# FRONT-UNIT-3_5.net
KiCad netlist of a schematic drawn in Altium Designer
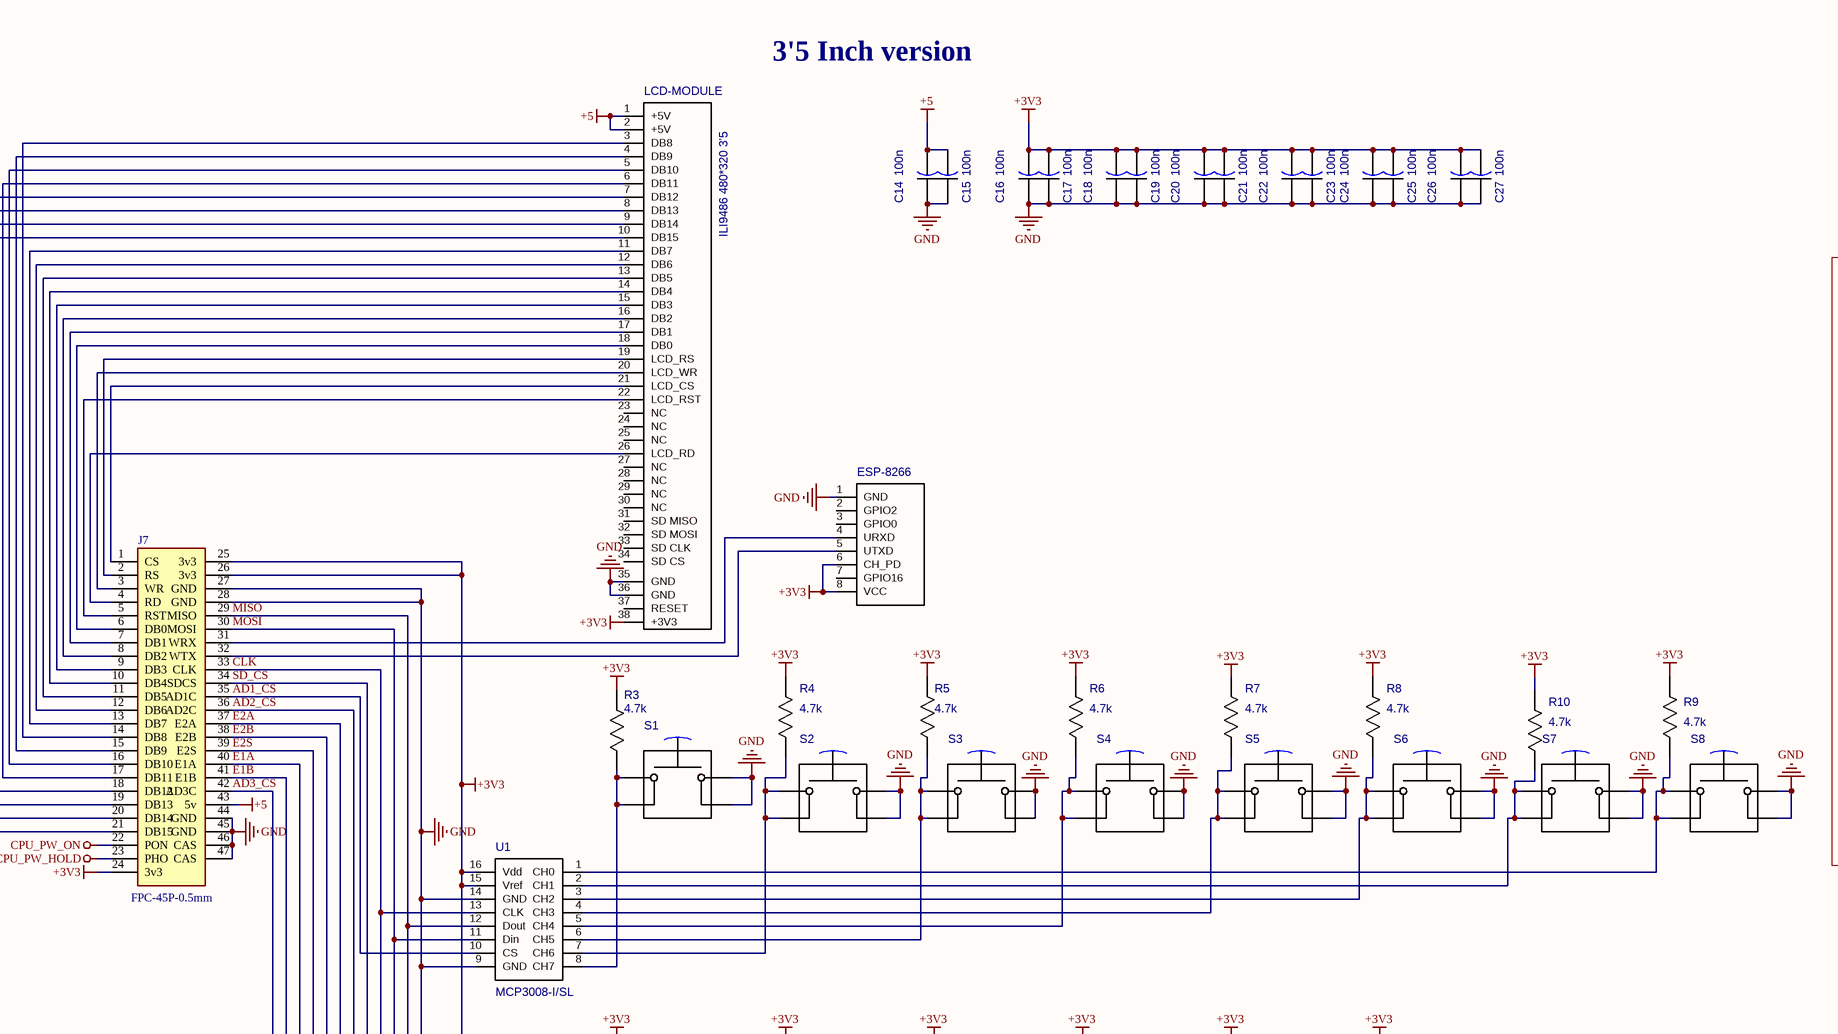
[diagram p0: FRONT-UNIT-3.5.SCHDOC, top left]
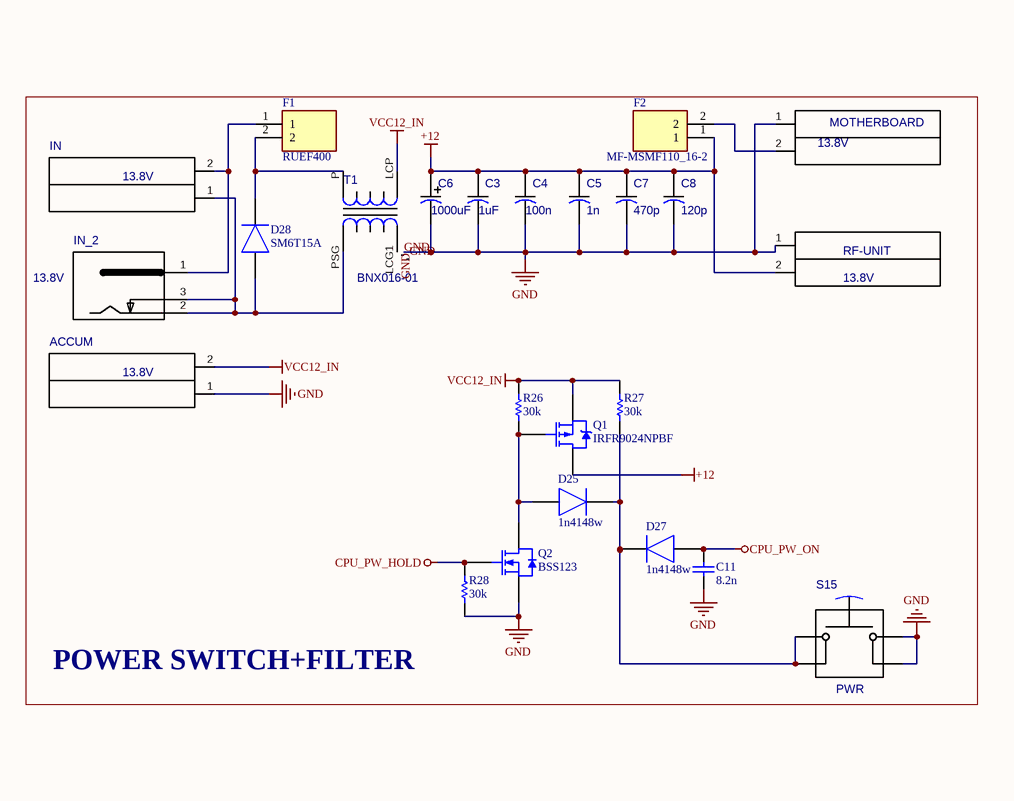
[diagram p1: FRONT-UNIT-3.5.SCHDOC, top right]
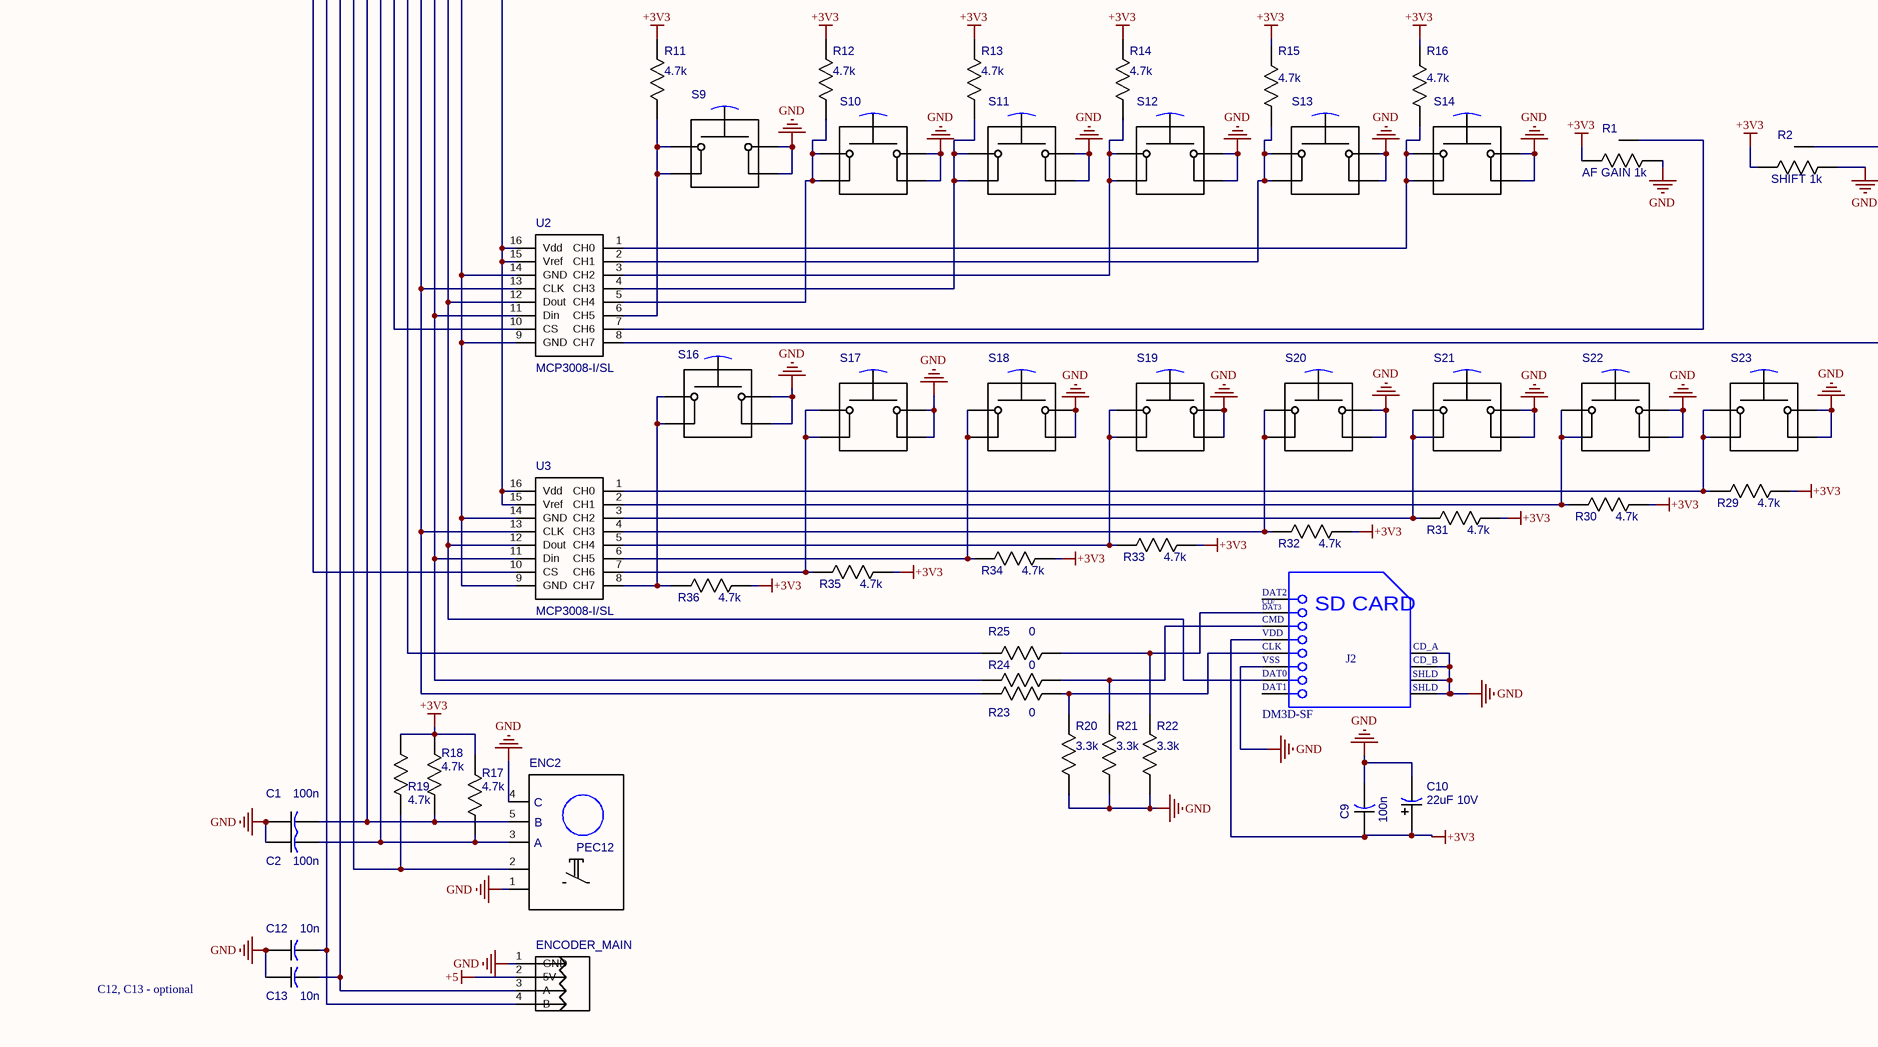
[diagram p2: FRONT-UNIT-3.5.SCHDOC, bottom left]
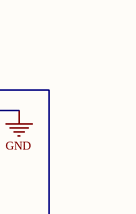
[diagram p3: FRONT-UNIT-3.5.SCHDOC, bottom right]

(export (version "E")
  (design (tool "Eeschema 10.0.6"))
  (components
    (comp (ref "ACCUM")
      (value "13.8V")
      (footprint "JX2")
      (description "JX2")
      (libsource (lib "*") (part "JX2"))
    )
    (comp (ref "C1")
      (value "100n")
      (footprint "CAP_0805")
      (description "CAP_0805")
      (libsource (lib "*") (part "CAP_0805"))
    )
    (comp (ref "C2")
      (value "100n")
      (footprint "CAP_0805")
      (description "CAP_0805")
      (libsource (lib "*") (part "CAP_0805"))
    )
    (comp (ref "C3")
      (value "1uF")
      (footprint "CAP_1206")
      (description "CAP_1206")
      (libsource (lib "*") (part "CAP_1206"))
    )
    (comp (ref "C4")
      (value "100n")
      (footprint "CAP_1206")
      (description "CAP_1206")
      (libsource (lib "*") (part "CAP_1206"))
    )
    (comp (ref "C5")
      (value "1n")
      (footprint "CAP_1206")
      (description "CAP_1206")
      (libsource (lib "*") (part "CAP_1206"))
    )
    (comp (ref "C6")
      (value "1000uF")
      (footprint "CAP250RP")
      (description "CAP250RP")
      (libsource (lib "*") (part "CAP250RP"))
    )
    (comp (ref "C7")
      (value "470p")
      (footprint "CAP_1206")
      (description "CAP_1206")
      (libsource (lib "*") (part "CAP_1206"))
    )
    (comp (ref "C8")
      (value "120p")
      (footprint "CAP_1206")
      (description "CAP_1206")
      (libsource (lib "*") (part "CAP_1206"))
    )
    (comp (ref "C9")
      (value "100n")
      (footprint "CAP_0805")
      (description "CAP_0805")
      (libsource (lib "*") (part "CAP_0805"))
    )
    (comp (ref "C10")
      (value "22uF 10V")
      (footprint "EEEFC_sizeB")
      (description "EEEFC_sizeB")
      (libsource (lib "*") (part "EEEFC_sizeB"))
    )
    (comp (ref "C11")
      (value "8.2n")
      (footprint "CAPC2013X94X50LL20T25")
      (description "CAP_1206")
      (fields
        (field (name "MANUFACTURER") "AVX Interconnect / Elco")
        (field (name "PART NUMBER") "08055C822KAT2A")
      )
      (libsource (lib "Altium Content Vault") (part "CAP"))
    )
    (comp (ref "C12")
      (value "10n")
      (footprint "CAP_0805")
      (description "CAP_0805")
      (libsource (lib "*") (part "CAP_0805"))
    )
    (comp (ref "C13")
      (value "10n")
      (footprint "CAP_0805")
      (description "CAP_0805")
      (libsource (lib "*") (part "CAP_0805"))
    )
    (comp (ref "C14")
      (value "100n")
      (footprint "CAP_0805")
      (description "CAP_0805")
      (libsource (lib "*") (part "CAP_0805"))
    )
    (comp (ref "C15")
      (value "100n")
      (footprint "CAP_0805")
      (description "CAP_0805")
      (libsource (lib "*") (part "CAP_0805"))
    )
    (comp (ref "C16")
      (value "100n")
      (footprint "CAP_0805")
      (description "CAP_0805")
      (libsource (lib "*") (part "CAP_0805"))
    )
    (comp (ref "C17")
      (value "100n")
      (footprint "CAP_0805")
      (description "CAP_0805")
      (libsource (lib "*") (part "CAP_0805"))
    )
    (comp (ref "C18")
      (value "100n")
      (footprint "CAP_0805")
      (description "CAP_0805")
      (libsource (lib "*") (part "CAP_0805"))
    )
    (comp (ref "C19")
      (value "100n")
      (footprint "CAP_0805")
      (description "CAP_0805")
      (libsource (lib "*") (part "CAP_0805"))
    )
    (comp (ref "C20")
      (value "100n")
      (footprint "CAP_0805")
      (description "CAP_0805")
      (libsource (lib "*") (part "CAP_0805"))
    )
    (comp (ref "C21")
      (value "100n")
      (footprint "CAP_0805")
      (description "CAP_0805")
      (libsource (lib "*") (part "CAP_0805"))
    )
    (comp (ref "C22")
      (value "100n")
      (footprint "CAP_0805")
      (description "CAP_0805")
      (libsource (lib "*") (part "CAP_0805"))
    )
    (comp (ref "C23")
      (value "100n")
      (footprint "CAP_0805")
      (description "CAP_0805")
      (libsource (lib "*") (part "CAP_0805"))
    )
    (comp (ref "C24")
      (value "100n")
      (footprint "CAP_0805")
      (description "CAP_0805")
      (libsource (lib "*") (part "CAP_0805"))
    )
    (comp (ref "C25")
      (value "100n")
      (footprint "CAP_0805")
      (description "CAP_0805")
      (libsource (lib "*") (part "CAP_0805"))
    )
    (comp (ref "C26")
      (value "100n")
      (footprint "CAP_0805")
      (description "CAP_0805")
      (libsource (lib "*") (part "CAP_0805"))
    )
    (comp (ref "C27")
      (value "100n")
      (footprint "CAP_0805")
      (description "CAP_0805")
      (libsource (lib "*") (part "CAP_0805"))
    )
    (comp (ref "D25")
      (value "1n4148w")
      (footprint "SamacSys:SOD3716X135N")
      (description "Diode")
      (libsource (lib "*") (part "1n4148w"))
    )
    (comp (ref "D27")
      (value "1n4148w")
      (footprint "SamacSys:SOD3716X135N")
      (description "Diode")
      (libsource (lib "*") (part "1n4148w"))
    )
    (comp (ref "D28")
      (value "SM6T15A")
      (footprint "SamacSys:SMBJ36CATR")
      (description "Diode")
      (fields (field (name "MOUSER PART NUMBER") "511-SM6T15A") (field (name "RS PART NUMBER") "4864915P"))
      (libsource (lib "*") (part "SM6T15A"))
    )
    (comp (ref "ENC2") (value "PEC12") (footprint "PEC12") (libsource (lib "*") (part "PEC12")))
    (comp (ref "ENCODER_MAIN")
      (value "OPTICAL ENCODER")
      (footprint "644456-4")
      (libsource (lib "*") (part "644456-4"))
    )
    (comp (ref "ESP-8266")
      (value "ESP-01 ESP8266")
      (footprint "ESP-01 ESP8266")
      (libsource (lib "*") (part "ESP-01 ESP8266"))
    )
    (comp (ref "F1")
      (value "RUEF400")
      (footprint "SamacSys:RUEF400")
      (description "Fuse")
      (fields (field (name "MOUSER PART NUMBER") "650-RUEF400") (field (name "RS PART NUMBER") "5176837P"))
      (libsource (lib "*") (part "RUEF400"))
    )
    (comp (ref "F2")
      (value "MF-MSMF110_16-2")
      (footprint "SamacSys:FUSC4632X85N")
      (description "Fuse")
      (fields
        (field (name "MANUFACTURER_PART_NUMBER") "MF-MSMF110/16-2")
        (field (name "MOUSER PART NUMBER") "652-MF-MSMF110/16-2")
      )
      (libsource (lib "*") (part "MF-MSMF110_16-2"))
    )
    (comp (ref "IN") (value "13.8V") (footprint "JX2") (description "JX2") (libsource (lib "*") (part "JX2")))
    (comp (ref "IN_2")
      (value "13.8V")
      (footprint "PJ-050B")
      (description "PJ-050B")
      (libsource (lib "*") (part "PJ-050B"))
    )
    (comp (ref "J2")
      (value "DM3D-SF")
      (footprint "HIRO-DM3D-SF_V")
      (fields (field (name "MANUFACTURER") "Hirose Electric"))
      (libsource (lib "Altium Content Vault") (part "CN-SD-8-2SW-2S"))
    )
    (comp (ref "J7")
      (value "FPC-45P-0.5mm")
      (footprint "FRONT-UNIT-3.5:FH12S45S05SH60")
      (description "Connector")
      (fields
        (field (name "MANUFACTURER_PART_NUMBER") "FH12S-45S-0.5SH(55)")
        (field (name "MOUSER PART NUMBER") "798-FH12S-45S-05SH55")
      )
      (libsource (lib "*") (part "FH12S-45S-0.5SH_55_"))
    )
    (comp (ref "LCD-MODULE")
      (value "ILI9486 480*320 3'5")
      (footprint "LCD-MODULE-3.2-480-320")
      (description "LCD-MODULE_3'2_480х320")
      (libsource (lib "FRONT-UNIT") (part "LCD-MODULE_3'2_480х320"))
    )
    (comp (ref "MOTHERBOARD")
      (value "13.8V")
      (footprint "JX2")
      (description "JX2")
      (libsource (lib "*") (part "JX2"))
    )
    (comp (ref "Q1")
      (value "IRFR9024NPBF")
      (footprint "ONSC-DPAK-3-369C-01_V")
      (description "IRFR9024NPBF, Транзистор, Р-канал 55В 11А")
      (fields (field (name "MANUFACTURER") "On Semiconductor") (field (name "PARTNUMBER") "NTD2955G"))
      (libsource (lib "Altium Content Vault") (part "ONSC-PMOS-G1S3D4-3_B"))
    )
    (comp (ref "Q2")
      (value "BSS123")
      (footprint "FAIR-SOT23-3_V")
      (fields (field (name "MANUFACTURER") "Fairchild"))
      (libsource (lib "Altium Content Vault") (part "NEMOS-GSD-3"))
    )
    (comp (ref "R1")
      (value "AF GAIN 1k")
      (footprint "PTV09")
      (description "Adjustable Resistor PTV09")
      (fields (field (name "Comment") "ptv09a-4225f-b102"))
      (libsource (lib "*") (part "PTV09"))
    )
    (comp (ref "R2")
      (value "SHIFT 1k")
      (footprint "PTV09")
      (description "Adjustable Resistor PTV09")
      (fields (field (name "Comment") "ptv09a-4225f-b102"))
      (libsource (lib "*") (part "PTV09"))
    )
    (comp (ref "R3")
      (value "4.7k")
      (footprint "RES_0805")
      (description "RES_0805")
      (libsource (lib "*") (part "RES_0805"))
    )
    (comp (ref "R4")
      (value "4.7k")
      (footprint "RES_0805")
      (description "RES_0805")
      (libsource (lib "*") (part "RES_0805"))
    )
    (comp (ref "R5")
      (value "4.7k")
      (footprint "RES_0805")
      (description "RES_0805")
      (libsource (lib "*") (part "RES_0805"))
    )
    (comp (ref "R6")
      (value "4.7k")
      (footprint "RES_0805")
      (description "RES_0805")
      (libsource (lib "*") (part "RES_0805"))
    )
    (comp (ref "R7")
      (value "4.7k")
      (footprint "RES_0805")
      (description "RES_0805")
      (libsource (lib "*") (part "RES_0805"))
    )
    (comp (ref "R8")
      (value "4.7k")
      (footprint "RES_0805")
      (description "RES_0805")
      (libsource (lib "*") (part "RES_0805"))
    )
    (comp (ref "R9")
      (value "4.7k")
      (footprint "RES_0805")
      (description "RES_0805")
      (libsource (lib "*") (part "RES_0805"))
    )
    (comp (ref "R10")
      (value "4.7k")
      (footprint "RES_0805")
      (description "RES_0805")
      (libsource (lib "*") (part "RES_0805"))
    )
    (comp (ref "R11")
      (value "4.7k")
      (footprint "RES_0805")
      (description "RES_0805")
      (libsource (lib "*") (part "RES_0805"))
    )
    (comp (ref "R12")
      (value "4.7k")
      (footprint "RES_0805")
      (description "RES_0805")
      (libsource (lib "*") (part "RES_0805"))
    )
    (comp (ref "R13")
      (value "4.7k")
      (footprint "RES_0805")
      (description "RES_0805")
      (libsource (lib "*") (part "RES_0805"))
    )
    (comp (ref "R14")
      (value "4.7k")
      (footprint "RES_0805")
      (description "RES_0805")
      (libsource (lib "*") (part "RES_0805"))
    )
    (comp (ref "R15")
      (value "4.7k")
      (footprint "RES_0805")
      (description "RES_0805")
      (libsource (lib "*") (part "RES_0805"))
    )
    (comp (ref "R16")
      (value "4.7k")
      (footprint "RES_0805")
      (description "RES_0805")
      (libsource (lib "*") (part "RES_0805"))
    )
    (comp (ref "R17")
      (value "4.7k")
      (footprint "RES_0805")
      (description "RES_0805")
      (libsource (lib "*") (part "RES_0805"))
    )
    (comp (ref "R18")
      (value "4.7k")
      (footprint "RES_0805")
      (description "RES_0805")
      (libsource (lib "*") (part "RES_0805"))
    )
    (comp (ref "R19")
      (value "4.7k")
      (footprint "RES_0805")
      (description "RES_0805")
      (libsource (lib "*") (part "RES_0805"))
    )
    (comp (ref "R20")
      (value "3.3k")
      (footprint "RES_0805")
      (description "RES_0805")
      (libsource (lib "*") (part "RES_0805"))
    )
    (comp (ref "R21")
      (value "3.3k")
      (footprint "RES_0805")
      (description "RES_0805")
      (libsource (lib "*") (part "RES_0805"))
    )
    (comp (ref "R22")
      (value "3.3k")
      (footprint "RES_0805")
      (description "RES_0805")
      (libsource (lib "*") (part "RES_0805"))
    )
    (comp (ref "R23")
      (value "0")
      (footprint "RES_0805")
      (description "RES_0805")
      (libsource (lib "*") (part "RES_0805"))
    )
    (comp (ref "R24")
      (value "0")
      (footprint "RES_0805")
      (description "RES_0805")
      (libsource (lib "*") (part "RES_0805"))
    )
    (comp (ref "R25")
      (value "0")
      (footprint "RES_0805")
      (description "RES_0805")
      (libsource (lib "*") (part "RES_0805"))
    )
    (comp (ref "R26")
      (value "30k")
      (footprint "RESC2013X60X40NL20T25")
      (description "RES_0805")
      (fields (field (name "MANUFACTURER") "Panasonic") (field (name "PART NUMBER") "ERA-6AEB303V"))
      (libsource (lib "Altium Content Vault") (part "RES"))
    )
    (comp (ref "R27")
      (value "30k")
      (footprint "RESC2013X60X40NL20T25")
      (description "RES_0805")
      (fields (field (name "MANUFACTURER") "Panasonic") (field (name "PART NUMBER") "ERA-6AEB303V"))
      (libsource (lib "Altium Content Vault") (part "RES"))
    )
    (comp (ref "R28")
      (value "30k")
      (footprint "RESC2013X60X40NL20T25")
      (description "RES_0805")
      (fields (field (name "MANUFACTURER") "Panasonic") (field (name "PART NUMBER") "ERA-6AEB303V"))
      (libsource (lib "Altium Content Vault") (part "RES"))
    )
    (comp (ref "R29")
      (value "4.7k")
      (footprint "RES_0805")
      (description "RES_0805")
      (libsource (lib "*") (part "RES_0805"))
    )
    (comp (ref "R30")
      (value "4.7k")
      (footprint "RES_0805")
      (description "RES_0805")
      (libsource (lib "*") (part "RES_0805"))
    )
    (comp (ref "R31")
      (value "4.7k")
      (footprint "RES_0805")
      (description "RES_0805")
      (libsource (lib "*") (part "RES_0805"))
    )
    (comp (ref "R32")
      (value "4.7k")
      (footprint "RES_0805")
      (description "RES_0805")
      (libsource (lib "*") (part "RES_0805"))
    )
    (comp (ref "R33")
      (value "4.7k")
      (footprint "RES_0805")
      (description "RES_0805")
      (libsource (lib "*") (part "RES_0805"))
    )
    (comp (ref "R34")
      (value "4.7k")
      (footprint "RES_0805")
      (description "RES_0805")
      (libsource (lib "*") (part "RES_0805"))
    )
    (comp (ref "R35")
      (value "4.7k")
      (footprint "RES_0805")
      (description "RES_0805")
      (libsource (lib "*") (part "RES_0805"))
    )
    (comp (ref "R36")
      (value "4.7k")
      (footprint "RES_0805")
      (description "RES_0805")
      (libsource (lib "*") (part "RES_0805"))
    )
    (comp (ref "RF-UNIT")
      (value "13.8V")
      (footprint "JX2")
      (description "JX2")
      (libsource (lib "*") (part "JX2"))
    )
    (comp (ref "S1")
      (value "PTS645SK50LFS")
      (footprint "PTS645SK50LFS")
      (fields (field (name "LCSC PART #") "test"))
      (libsource (lib "*") (part "PTS645SK50LFS"))
    )
    (comp (ref "S2")
      (value "PTS645SK50LFS")
      (footprint "PTS645SK50LFS")
      (libsource (lib "*") (part "PTS645SK50LFS"))
    )
    (comp (ref "S3")
      (value "PTS645SK50LFS")
      (footprint "PTS645SK50LFS")
      (libsource (lib "*") (part "PTS645SK50LFS"))
    )
    (comp (ref "S4")
      (value "PTS645SK50LFS")
      (footprint "PTS645SK50LFS")
      (libsource (lib "*") (part "PTS645SK50LFS"))
    )
    (comp (ref "S5")
      (value "PTS645SK50LFS")
      (footprint "PTS645SK50LFS")
      (libsource (lib "*") (part "PTS645SK50LFS"))
    )
    (comp (ref "S6")
      (value "PTS645SK50LFS")
      (footprint "PTS645SK50LFS")
      (libsource (lib "*") (part "PTS645SK50LFS"))
    )
    (comp (ref "S7")
      (value "PTS645SK50LFS")
      (footprint "PTS645SK50LFS")
      (libsource (lib "*") (part "PTS645SK50LFS"))
    )
    (comp (ref "S8")
      (value "PTS645SK50LFS")
      (footprint "PTS645SK50LFS")
      (libsource (lib "*") (part "PTS645SK50LFS"))
    )
    (comp (ref "S9")
      (value "PTS645SK50LFS")
      (footprint "PTS645SK50LFS")
      (libsource (lib "*") (part "PTS645SK50LFS"))
    )
    (comp (ref "S10")
      (value "PTS645SK50LFS")
      (footprint "PTS645SK50LFS")
      (libsource (lib "*") (part "PTS645SK50LFS"))
    )
    (comp (ref "S11")
      (value "PTS645SK50LFS")
      (footprint "PTS645SK50LFS")
      (libsource (lib "*") (part "PTS645SK50LFS"))
    )
    (comp (ref "S12")
      (value "PTS645SK50LFS")
      (footprint "PTS645SK50LFS")
      (libsource (lib "*") (part "PTS645SK50LFS"))
    )
    (comp (ref "S13")
      (value "PTS645SK50LFS")
      (footprint "PTS645SK50LFS")
      (libsource (lib "*") (part "PTS645SK50LFS"))
    )
    (comp (ref "S14")
      (value "PTS645SK50LFS")
      (footprint "PTS645SK50LFS")
      (libsource (lib "*") (part "PTS645SK50LFS"))
    )
    (comp (ref "S15")
      (value "PWR")
      (footprint "PTS645SK50LFS")
      (description "PTS645SK50LFS")
      (libsource (lib "*") (part "PTS645SK50LFS"))
    )
    (comp (ref "S16")
      (value "PTS645SK50LFS")
      (footprint "PTS645SK50LFS")
      (libsource (lib "*") (part "PTS645SK50LFS"))
    )
    (comp (ref "S17")
      (value "PTS645SK50LFS")
      (footprint "PTS645SK50LFS")
      (libsource (lib "*") (part "PTS645SK50LFS"))
    )
    (comp (ref "S18")
      (value "PTS645SK50LFS")
      (footprint "PTS645SK50LFS")
      (libsource (lib "*") (part "PTS645SK50LFS"))
    )
    (comp (ref "S19")
      (value "PTS645SK50LFS")
      (footprint "PTS645SK50LFS")
      (libsource (lib "*") (part "PTS645SK50LFS"))
    )
    (comp (ref "S20")
      (value "PTS645SK50LFS")
      (footprint "PTS645SK50LFS")
      (libsource (lib "*") (part "PTS645SK50LFS"))
    )
    (comp (ref "S21")
      (value "PTS645SK50LFS")
      (footprint "PTS645SK50LFS")
      (libsource (lib "*") (part "PTS645SK50LFS"))
    )
    (comp (ref "S22")
      (value "PTS645SK50LFS")
      (footprint "PTS645SK50LFS")
      (libsource (lib "*") (part "PTS645SK50LFS"))
    )
    (comp (ref "S23")
      (value "PTS645SK50LFS")
      (footprint "PTS645SK50LFS")
      (libsource (lib "*") (part "PTS645SK50LFS"))
    )
    (comp (ref "T1")
      (value "BNX016-01")
      (footprint "TRANSF_ICORE")
      (libsource (lib "*") (part "TRANSF_ICORE"))
    )
    (comp (ref "U1")
      (value "MCP3008-I/SL")
      (footprint "MCP3008-I/SL")
      (libsource (lib "*") (part "MCP3008-I/SL"))
    )
    (comp (ref "U2")
      (value "MCP3008-I/SL")
      (footprint "MCP3008-I/SL")
      (libsource (lib "*") (part "MCP3008-I/SL"))
    )
    (comp (ref "U3")
      (value "MCP3008-I/SL")
      (footprint "MCP3008-I/SL")
      (libsource (lib "*") (part "MCP3008-I/SL"))
    )
  )
  (nets
    (net (code "1") (name "+3V3") (class "Default")
      (node (ref "C10") (pin "1") (pinfunction "PLUS_1") (pintype "passive"))
      (node (ref "C16") (pin "2") (pinfunction "2_2") (pintype "passive"))
      (node (ref "C17") (pin "2") (pinfunction "2_2") (pintype "passive"))
      (node (ref "C18") (pin "2") (pinfunction "2_2") (pintype "passive"))
      (node (ref "C19") (pin "2") (pinfunction "2_2") (pintype "passive"))
      (node (ref "C20") (pin "2") (pinfunction "2_2") (pintype "passive"))
      (node (ref "C21") (pin "2") (pinfunction "2_2") (pintype "passive"))
      (node (ref "C22") (pin "2") (pinfunction "2_2") (pintype "passive"))
      (node (ref "C23") (pin "2") (pinfunction "2_2") (pintype "passive"))
      (node (ref "C24") (pin "2") (pinfunction "2_2") (pintype "passive"))
      (node (ref "C25") (pin "2") (pinfunction "2_2") (pintype "passive"))
      (node (ref "C26") (pin "2") (pinfunction "2_2") (pintype "passive"))
      (node (ref "C27") (pin "2") (pinfunction "2_2") (pintype "passive"))
      (node (ref "C9") (pin "1") (pinfunction "1_1") (pintype "passive"))
      (node (ref "ESP-8266") (pin "6") (pinfunction "CH_PD_6") (pintype "passive"))
      (node (ref "ESP-8266") (pin "8") (pinfunction "VCC_8") (pintype "passive"))
      (node (ref "J2") (pin "4") (pinfunction "VDD_4") (pintype "passive"))
      (node (ref "J7") (pin "24") (pinfunction "3v3_24") (pintype "passive"))
      (node (ref "J7") (pin "25") (pinfunction "3v3_25") (pintype "passive"))
      (node (ref "J7") (pin "26") (pinfunction "3v3_26") (pintype "passive"))
      (node (ref "LCD-MODULE") (pin "38") (pinfunction "+3V3_38") (pintype "passive"))
      (node (ref "R1") (pin "1") (pinfunction "CW_1") (pintype "passive"))
      (node (ref "R10") (pin "2") (pinfunction "2_2") (pintype "passive"))
      (node (ref "R11") (pin "2") (pinfunction "2_2") (pintype "passive"))
      (node (ref "R12") (pin "2") (pinfunction "2_2") (pintype "passive"))
      (node (ref "R13") (pin "2") (pinfunction "2_2") (pintype "passive"))
      (node (ref "R14") (pin "2") (pinfunction "2_2") (pintype "passive"))
      (node (ref "R15") (pin "2") (pinfunction "2_2") (pintype "passive"))
      (node (ref "R16") (pin "2") (pinfunction "2_2") (pintype "passive"))
      (node (ref "R17") (pin "2") (pinfunction "2_2") (pintype "passive"))
      (node (ref "R18") (pin "2") (pinfunction "2_2") (pintype "passive"))
      (node (ref "R19") (pin "2") (pinfunction "2_2") (pintype "passive"))
      (node (ref "R2") (pin "1") (pinfunction "CW_1") (pintype "passive"))
      (node (ref "R29") (pin "2") (pinfunction "2_2") (pintype "passive"))
      (node (ref "R3") (pin "2") (pinfunction "2_2") (pintype "passive"))
      (node (ref "R30") (pin "2") (pinfunction "2_2") (pintype "passive"))
      (node (ref "R31") (pin "2") (pinfunction "2_2") (pintype "passive"))
      (node (ref "R32") (pin "2") (pinfunction "2_2") (pintype "passive"))
      (node (ref "R33") (pin "2") (pinfunction "2_2") (pintype "passive"))
      (node (ref "R34") (pin "2") (pinfunction "2_2") (pintype "passive"))
      (node (ref "R35") (pin "2") (pinfunction "2_2") (pintype "passive"))
      (node (ref "R36") (pin "2") (pinfunction "2_2") (pintype "passive"))
      (node (ref "R4") (pin "2") (pinfunction "2_2") (pintype "passive"))
      (node (ref "R5") (pin "2") (pinfunction "2_2") (pintype "passive"))
      (node (ref "R6") (pin "2") (pinfunction "2_2") (pintype "passive"))
      (node (ref "R7") (pin "2") (pinfunction "2_2") (pintype "passive"))
      (node (ref "R8") (pin "2") (pinfunction "2_2") (pintype "passive"))
      (node (ref "R9") (pin "2") (pinfunction "2_2") (pintype "passive"))
      (node (ref "U1") (pin "15") (pinfunction "Vref_15") (pintype "passive"))
      (node (ref "U1") (pin "16") (pinfunction "Vdd_16") (pintype "passive"))
      (node (ref "U2") (pin "15") (pinfunction "Vref_15") (pintype "passive"))
      (node (ref "U2") (pin "16") (pinfunction "Vdd_16") (pintype "passive"))
      (node (ref "U3") (pin "15") (pinfunction "Vref_15") (pintype "passive"))
      (node (ref "U3") (pin "16") (pinfunction "Vdd_16") (pintype "passive"))
    )
    (net (code "2") (name "+5") (class "Default")
      (node (ref "C14") (pin "2") (pinfunction "2_2") (pintype "passive"))
      (node (ref "C15") (pin "2") (pinfunction "2_2") (pintype "passive"))
      (node (ref "ENCODER_MAIN") (pin "2") (pinfunction "5V_2") (pintype "passive"))
      (node (ref "J7") (pin "43") (pinfunction "5v_43") (pintype "passive"))
      (node (ref "LCD-MODULE") (pin "1") (pinfunction "+5V_1") (pintype "passive"))
      (node (ref "LCD-MODULE") (pin "2") (pinfunction "+5V_2") (pintype "passive"))
    )
    (net (code "3") (name "+12") (class "Default")
      (node (ref "C3") (pin "1") (pinfunction "1_1") (pintype "passive"))
      (node (ref "C4") (pin "1") (pinfunction "1_1") (pintype "passive"))
      (node (ref "C5") (pin "1") (pinfunction "1_1") (pintype "passive"))
      (node (ref "C6") (pin "1") (pinfunction "PLUS_1") (pintype "passive"))
      (node (ref "C7") (pin "1") (pinfunction "1_1") (pintype "passive"))
      (node (ref "C8") (pin "1") (pinfunction "1_1") (pintype "passive"))
      (node (ref "F2") (pin "1") (pinfunction "1_1") (pintype "passive"))
      (node (ref "Q1") (pin "4") (pinfunction "D_4") (pintype "passive"))
      (node (ref "RF-UNIT") (pin "2") (pinfunction "1_2") (pintype "passive"))
    )
    (net (code "4") (name "/AD1_CS") (class "Default")
      (node (ref "J7") (pin "35") (pinfunction "AD1C_35") (pintype "passive"))
      (node (ref "U1") (pin "10") (pinfunction "CS_10") (pintype "passive"))
    )
    (net (code "5") (name "/AD2_CS") (class "Default")
      (node (ref "J7") (pin "36") (pinfunction "AD2C_36") (pintype "passive"))
      (node (ref "U2") (pin "10") (pinfunction "CS_10") (pintype "passive"))
    )
    (net (code "6") (name "/AD3_CS") (class "Default")
      (node (ref "J7") (pin "42") (pinfunction "AD3C_42") (pintype "passive"))
      (node (ref "U3") (pin "10") (pinfunction "CS_10") (pintype "passive"))
    )
    (net (code "7") (name "/CLK") (class "Default")
      (node (ref "J7") (pin "33") (pinfunction "CLK_33") (pintype "passive"))
      (node (ref "R23") (pin "2") (pinfunction "2_2") (pintype "passive"))
      (node (ref "U1") (pin "13") (pinfunction "CLK_13") (pintype "passive"))
      (node (ref "U2") (pin "13") (pinfunction "CLK_13") (pintype "passive"))
      (node (ref "U3") (pin "13") (pinfunction "CLK_13") (pintype "passive"))
    )
    (net (code "8") (name "/E1A") (class "Default")
      (node (ref "C13") (pin "2") (pinfunction "2_2") (pintype "passive"))
      (node (ref "ENCODER_MAIN") (pin "3") (pinfunction "A_3") (pintype "passive"))
      (node (ref "J7") (pin "40") (pinfunction "E1A_40") (pintype "passive"))
    )
    (net (code "9") (name "/E1B") (class "Default")
      (node (ref "C12") (pin "2") (pinfunction "2_2") (pintype "passive"))
      (node (ref "ENCODER_MAIN") (pin "4") (pinfunction "B_4") (pintype "passive"))
      (node (ref "J7") (pin "41") (pinfunction "E1B_41") (pintype "passive"))
    )
    (net (code "10") (name "/E2A") (class "Default")
      (node (ref "C2") (pin "2") (pinfunction "2_2") (pintype "passive"))
      (node (ref "ENC2") (pin "3") (pinfunction "A_3") (pintype "passive"))
      (node (ref "J7") (pin "37") (pinfunction "E2A_37") (pintype "passive"))
      (node (ref "R17") (pin "1") (pinfunction "1_1") (pintype "passive"))
    )
    (net (code "11") (name "/E2B") (class "Default")
      (node (ref "C1") (pin "2") (pinfunction "2_2") (pintype "passive"))
      (node (ref "ENC2") (pin "5") (pinfunction "B_5") (pintype "passive"))
      (node (ref "J7") (pin "38") (pinfunction "E2B_38") (pintype "passive"))
      (node (ref "R18") (pin "1") (pinfunction "1_1") (pintype "passive"))
    )
    (net (code "12") (name "/E2S") (class "Default")
      (node (ref "ENC2") (pin "2") (pinfunction "2_2") (pintype "passive"))
      (node (ref "J7") (pin "39") (pinfunction "E2S_39") (pintype "passive"))
      (node (ref "R19") (pin "1") (pinfunction "1_1") (pintype "passive"))
    )
    (net (code "13") (name "/MISO") (class "Default")
      (node (ref "J2") (pin "7") (pinfunction "DAT0_7") (pintype "passive"))
      (node (ref "J7") (pin "29") (pinfunction "MISO_29") (pintype "passive"))
      (node (ref "U1") (pin "12") (pinfunction "Dout_12") (pintype "passive"))
      (node (ref "U2") (pin "12") (pinfunction "Dout_12") (pintype "passive"))
      (node (ref "U3") (pin "12") (pinfunction "Dout_12") (pintype "passive"))
    )
    (net (code "14") (name "/MOSI") (class "Default")
      (node (ref "J7") (pin "30") (pinfunction "MOSI_30") (pintype "passive"))
      (node (ref "R24") (pin "2") (pinfunction "2_2") (pintype "passive"))
      (node (ref "U1") (pin "11") (pinfunction "Din_11") (pintype "passive"))
      (node (ref "U2") (pin "11") (pinfunction "Din_11") (pintype "passive"))
      (node (ref "U3") (pin "11") (pinfunction "Din_11") (pintype "passive"))
    )
    (net (code "15") (name "/SD_CS") (class "Default")
      (node (ref "J7") (pin "34") (pinfunction "SDCS_34") (pintype "passive"))
      (node (ref "R25") (pin "2") (pinfunction "2_2") (pintype "passive"))
    )
    (net (code "16") (name "CPU_PW_HOLD") (class "Default")
      (node (ref "J7") (pin "23") (pinfunction "PHO_23") (pintype "passive"))
      (node (ref "Q2") (pin "1") (pinfunction "G_1") (pintype "passive"))
      (node (ref "R28") (pin "2") (pinfunction "2_2") (pintype "passive"))
    )
    (net (code "17") (name "CPU_PW_ON") (class "Default")
      (node (ref "C11") (pin "2") (pinfunction "2_2") (pintype "passive"))
      (node (ref "D27") (pin "2") (pinfunction "A_2") (pintype "passive"))
      (node (ref "J7") (pin "22") (pinfunction "PON_22") (pintype "passive"))
    )
    (net (code "18") (name "GND") (class "Default")
      (node (ref "ACCUM") (pin "1") (pinfunction "2_1") (pintype "passive"))
      (node (ref "C1") (pin "1") (pinfunction "1_1") (pintype "passive"))
      (node (ref "C10") (pin "2") (pinfunction "MINUS_2") (pintype "passive"))
      (node (ref "C11") (pin "1") (pinfunction "1_1") (pintype "passive"))
      (node (ref "C12") (pin "1") (pinfunction "1_1") (pintype "passive"))
      (node (ref "C13") (pin "1") (pinfunction "1_1") (pintype "passive"))
      (node (ref "C14") (pin "1") (pinfunction "1_1") (pintype "passive"))
      (node (ref "C15") (pin "1") (pinfunction "1_1") (pintype "passive"))
      (node (ref "C16") (pin "1") (pinfunction "1_1") (pintype "passive"))
      (node (ref "C17") (pin "1") (pinfunction "1_1") (pintype "passive"))
      (node (ref "C18") (pin "1") (pinfunction "1_1") (pintype "passive"))
      (node (ref "C19") (pin "1") (pinfunction "1_1") (pintype "passive"))
      (node (ref "C2") (pin "1") (pinfunction "1_1") (pintype "passive"))
      (node (ref "C20") (pin "1") (pinfunction "1_1") (pintype "passive"))
      (node (ref "C21") (pin "1") (pinfunction "1_1") (pintype "passive"))
      (node (ref "C22") (pin "1") (pinfunction "1_1") (pintype "passive"))
      (node (ref "C23") (pin "1") (pinfunction "1_1") (pintype "passive"))
      (node (ref "C24") (pin "1") (pinfunction "1_1") (pintype "passive"))
      (node (ref "C25") (pin "1") (pinfunction "1_1") (pintype "passive"))
      (node (ref "C26") (pin "1") (pinfunction "1_1") (pintype "passive"))
      (node (ref "C27") (pin "1") (pinfunction "1_1") (pintype "passive"))
      (node (ref "C3") (pin "2") (pinfunction "2_2") (pintype "passive"))
      (node (ref "C4") (pin "2") (pinfunction "2_2") (pintype "passive"))
      (node (ref "C5") (pin "2") (pinfunction "2_2") (pintype "passive"))
      (node (ref "C6") (pin "2") (pinfunction "MINUS_2") (pintype "passive"))
      (node (ref "C7") (pin "2") (pinfunction "2_2") (pintype "passive"))
      (node (ref "C8") (pin "2") (pinfunction "2_2") (pintype "passive"))
      (node (ref "C9") (pin "2") (pinfunction "2_2") (pintype "passive"))
      (node (ref "ENC2") (pin "1") (pinfunction "1_1") (pintype "passive"))
      (node (ref "ENC2") (pin "4") (pinfunction "C_4") (pintype "passive"))
      (node (ref "ENCODER_MAIN") (pin "1") (pinfunction "GND_1") (pintype "passive"))
      (node (ref "ESP-8266") (pin "1") (pinfunction "GND_1") (pintype "passive"))
      (node (ref "J2") (pin "10") (pinfunction "CD_B_10") (pintype "passive"))
      (node (ref "J2") (pin "11") (pinfunction "SHLD1_11") (pintype "passive"))
      (node (ref "J2") (pin "12") (pinfunction "SHLD2_12") (pintype "passive"))
      (node (ref "J2") (pin "13") (pinfunction "SHLD3_13") (pintype "passive"))
      (node (ref "J2") (pin "14") (pinfunction "SHLD4_14") (pintype "passive"))
      (node (ref "J2") (pin "6") (pinfunction "VSS2_6") (pintype "passive"))
      (node (ref "J2") (pin "9") (pinfunction "CD_A_9") (pintype "passive"))
      (node (ref "J7") (pin "27") (pinfunction "GND_27") (pintype "passive"))
      (node (ref "J7") (pin "28") (pinfunction "GND_28") (pintype "passive"))
      (node (ref "J7") (pin "44") (pinfunction "GND_44") (pintype "passive"))
      (node (ref "J7") (pin "45") (pinfunction "GND_45") (pintype "passive"))
      (node (ref "J7") (pin "46") (pinfunction "CAS_46") (pintype "passive"))
      (node (ref "J7") (pin "47") (pinfunction "CAS_47") (pintype "passive"))
      (node (ref "LCD-MODULE") (pin "35") (pinfunction "GND_35") (pintype "passive"))
      (node (ref "LCD-MODULE") (pin "36") (pinfunction "GND_36") (pintype "passive"))
      (node (ref "MOTHERBOARD") (pin "1") (pinfunction "2_1") (pintype "passive"))
      (node (ref "Q2") (pin "2") (pinfunction "S_2") (pintype "passive"))
      (node (ref "R1") (pin "3") (pinfunction "CCW_3") (pintype "passive"))
      (node (ref "R2") (pin "3") (pinfunction "CCW_3") (pintype "passive"))
      (node (ref "R20") (pin "1") (pinfunction "1_1") (pintype "passive"))
      (node (ref "R21") (pin "1") (pinfunction "1_1") (pintype "passive"))
      (node (ref "R22") (pin "1") (pinfunction "1_1") (pintype "passive"))
      (node (ref "R28") (pin "1") (pinfunction "1_1") (pintype "passive"))
      (node (ref "RF-UNIT") (pin "1") (pinfunction "2_1") (pintype "passive"))
      (node (ref "S1") (pin "3") (pinfunction "B_3") (pintype "passive"))
      (node (ref "S1") (pin "4") (pinfunction "B_4") (pintype "passive"))
      (node (ref "S10") (pin "3") (pinfunction "B_3") (pintype "passive"))
      (node (ref "S10") (pin "4") (pinfunction "B_4") (pintype "passive"))
      (node (ref "S11") (pin "3") (pinfunction "B_3") (pintype "passive"))
      (node (ref "S11") (pin "4") (pinfunction "B_4") (pintype "passive"))
      (node (ref "S12") (pin "3") (pinfunction "B_3") (pintype "passive"))
      (node (ref "S12") (pin "4") (pinfunction "B_4") (pintype "passive"))
      (node (ref "S13") (pin "3") (pinfunction "B_3") (pintype "passive"))
      (node (ref "S13") (pin "4") (pinfunction "B_4") (pintype "passive"))
      (node (ref "S14") (pin "3") (pinfunction "B_3") (pintype "passive"))
      (node (ref "S14") (pin "4") (pinfunction "B_4") (pintype "passive"))
      (node (ref "S15") (pin "3") (pinfunction "B_3") (pintype "passive"))
      (node (ref "S15") (pin "4") (pinfunction "B_4") (pintype "passive"))
      (node (ref "S16") (pin "3") (pinfunction "B_3") (pintype "passive"))
      (node (ref "S16") (pin "4") (pinfunction "B_4") (pintype "passive"))
      (node (ref "S17") (pin "3") (pinfunction "B_3") (pintype "passive"))
      (node (ref "S17") (pin "4") (pinfunction "B_4") (pintype "passive"))
      (node (ref "S18") (pin "3") (pinfunction "B_3") (pintype "passive"))
      (node (ref "S18") (pin "4") (pinfunction "B_4") (pintype "passive"))
      (node (ref "S19") (pin "3") (pinfunction "B_3") (pintype "passive"))
      (node (ref "S19") (pin "4") (pinfunction "B_4") (pintype "passive"))
      (node (ref "S2") (pin "3") (pinfunction "B_3") (pintype "passive"))
      (node (ref "S2") (pin "4") (pinfunction "B_4") (pintype "passive"))
      (node (ref "S20") (pin "3") (pinfunction "B_3") (pintype "passive"))
      (node (ref "S20") (pin "4") (pinfunction "B_4") (pintype "passive"))
      (node (ref "S21") (pin "3") (pinfunction "B_3") (pintype "passive"))
      (node (ref "S21") (pin "4") (pinfunction "B_4") (pintype "passive"))
      (node (ref "S22") (pin "3") (pinfunction "B_3") (pintype "passive"))
      (node (ref "S22") (pin "4") (pinfunction "B_4") (pintype "passive"))
      (node (ref "S23") (pin "3") (pinfunction "B_3") (pintype "passive"))
      (node (ref "S23") (pin "4") (pinfunction "B_4") (pintype "passive"))
      (node (ref "S3") (pin "3") (pinfunction "B_3") (pintype "passive"))
      (node (ref "S3") (pin "4") (pinfunction "B_4") (pintype "passive"))
      (node (ref "S4") (pin "3") (pinfunction "B_3") (pintype "passive"))
      (node (ref "S4") (pin "4") (pinfunction "B_4") (pintype "passive"))
      (node (ref "S5") (pin "3") (pinfunction "B_3") (pintype "passive"))
      (node (ref "S5") (pin "4") (pinfunction "B_4") (pintype "passive"))
      (node (ref "S6") (pin "3") (pinfunction "B_3") (pintype "passive"))
      (node (ref "S6") (pin "4") (pinfunction "B_4") (pintype "passive"))
      (node (ref "S7") (pin "3") (pinfunction "B_3") (pintype "passive"))
      (node (ref "S7") (pin "4") (pinfunction "B_4") (pintype "passive"))
      (node (ref "S8") (pin "3") (pinfunction "B_3") (pintype "passive"))
      (node (ref "S8") (pin "4") (pinfunction "B_4") (pintype "passive"))
      (node (ref "S9") (pin "3") (pinfunction "B_3") (pintype "passive"))
      (node (ref "S9") (pin "4") (pinfunction "B_4") (pintype "passive"))
      (node (ref "T1") (pin "LCG1") (pinfunction "S2_LCG1") (pintype "passive"))
      (node (ref "T1") (pin "LCG2") (pinfunction "0_LCG2") (pintype "passive"))
      (node (ref "T1") (pin "LCG3") (pinfunction "0_LCG3") (pintype "passive"))
      (node (ref "U1") (pin "14") (pinfunction "GND_14") (pintype "passive"))
      (node (ref "U1") (pin "9") (pinfunction "GND_9") (pintype "passive"))
      (node (ref "U2") (pin "14") (pinfunction "GND_14") (pintype "passive"))
      (node (ref "U2") (pin "9") (pinfunction "GND_9") (pintype "passive"))
      (node (ref "U3") (pin "14") (pinfunction "GND_14") (pintype "passive"))
      (node (ref "U3") (pin "9") (pinfunction "GND_9") (pintype "passive"))
    )
    (net (code "19") (name "Net-(D25-A)") (class "Default")
      (node (ref "D25") (pin "2") (pinfunction "A_2") (pintype "passive"))
      (node (ref "Q1") (pin "1") (pinfunction "G_1") (pintype "passive"))
      (node (ref "Q2") (pin "3") (pinfunction "D_3") (pintype "passive"))
      (node (ref "R26") (pin "1") (pinfunction "1_1") (pintype "passive"))
    )
    (net (code "20") (name "Net-(D25-K)") (class "Default")
      (node (ref "D25") (pin "1") (pinfunction "K_1") (pintype "passive"))
      (node (ref "D27") (pin "1") (pinfunction "K_1") (pintype "passive"))
      (node (ref "R27") (pin "1") (pinfunction "1_1") (pintype "passive"))
      (node (ref "S15") (pin "1") (pinfunction "A_1") (pintype "passive"))
      (node (ref "S15") (pin "2") (pinfunction "A_2") (pintype "passive"))
    )
    (net (code "21") (name "Net-(D28-A)") (class "Default")
      (node (ref "D28") (pin "2") (pinfunction "A_2") (pintype "passive"))
      (node (ref "IN") (pin "1") (pinfunction "2_1") (pintype "passive"))
      (node (ref "IN_2") (pin "2") (pinfunction "2_2") (pintype "passive"))
      (node (ref "IN_2") (pin "3") (pinfunction "3_3") (pintype "passive"))
      (node (ref "T1") (pin "PSG") (pinfunction "S1_PSG") (pintype "passive"))
    )
    (net (code "22") (name "Net-(D28-K)") (class "Default")
      (node (ref "D28") (pin "1") (pinfunction "K_1") (pintype "passive"))
      (node (ref "F1") (pin "2") (pinfunction "2_2") (pintype "passive"))
      (node (ref "T1") (pin "P") (pinfunction "P1_P") (pintype "passive"))
    )
    (net (code "23") (name "Net-(ESP-8266-URXD)") (class "Default")
      (node (ref "ESP-8266") (pin "4") (pinfunction "URXD_4") (pintype "passive"))
      (node (ref "J7") (pin "31") (pinfunction "WRX_31") (pintype "passive"))
    )
    (net (code "24") (name "Net-(ESP-8266-UTXD)") (class "Default")
      (node (ref "ESP-8266") (pin "5") (pinfunction "UTXD_5") (pintype "passive"))
      (node (ref "J7") (pin "32") (pinfunction "WTX_32") (pintype "passive"))
    )
    (net (code "25") (name "Net-(IN-1)") (class "Default")
      (node (ref "F1") (pin "1") (pinfunction "1_1") (pintype "passive"))
      (node (ref "IN") (pin "2") (pinfunction "1_2") (pintype "passive"))
      (node (ref "IN_2") (pin "1") (pinfunction "1_1") (pintype "passive"))
    )
    (net (code "26") (name "Net-(J2-CLK)") (class "Default")
      (node (ref "J2") (pin "5") (pinfunction "CLK_5") (pintype "passive"))
      (node (ref "R20") (pin "2") (pinfunction "2_2") (pintype "passive"))
      (node (ref "R23") (pin "1") (pinfunction "1_1") (pintype "passive"))
    )
    (net (code "27") (name "Net-(J2-CMD)") (class "Default")
      (node (ref "J2") (pin "2") (pinfunction "CMD_2") (pintype "passive"))
      (node (ref "R22") (pin "2") (pinfunction "2_2") (pintype "passive"))
      (node (ref "R25") (pin "1") (pinfunction "1_1") (pintype "passive"))
    )
    (net (code "28") (name "Net-(J2-VSS1)") (class "Default")
      (node (ref "J2") (pin "3") (pinfunction "VSS1_3") (pintype "passive"))
      (node (ref "R21") (pin "2") (pinfunction "2_2") (pintype "passive"))
      (node (ref "R24") (pin "1") (pinfunction "1_1") (pintype "passive"))
    )
    (net (code "29") (name "Net-(J7-CS)") (class "Default")
      (node (ref "J7") (pin "1") (pinfunction "CS_1") (pintype "passive"))
      (node (ref "LCD-MODULE") (pin "21") (pinfunction "LCD_CS_21") (pintype "passive"))
    )
    (net (code "30") (name "Net-(J7-DB0)") (class "Default")
      (node (ref "J7") (pin "6") (pinfunction "DB0_6") (pintype "passive"))
      (node (ref "LCD-MODULE") (pin "18") (pinfunction "DB0_18") (pintype "passive"))
    )
    (net (code "31") (name "Net-(J7-DB1)") (class "Default")
      (node (ref "J7") (pin "7") (pinfunction "DB1_7") (pintype "passive"))
      (node (ref "LCD-MODULE") (pin "17") (pinfunction "DB1_17") (pintype "passive"))
    )
    (net (code "32") (name "Net-(J7-DB2)") (class "Default")
      (node (ref "J7") (pin "8") (pinfunction "DB2_8") (pintype "passive"))
      (node (ref "LCD-MODULE") (pin "16") (pinfunction "DB2_16") (pintype "passive"))
    )
    (net (code "33") (name "Net-(J7-DB3)") (class "Default")
      (node (ref "J7") (pin "9") (pinfunction "DB3_9") (pintype "passive"))
      (node (ref "LCD-MODULE") (pin "15") (pinfunction "DB3_15") (pintype "passive"))
    )
    (net (code "34") (name "Net-(J7-DB4)") (class "Default")
      (node (ref "J7") (pin "10") (pinfunction "DB4_10") (pintype "passive"))
      (node (ref "LCD-MODULE") (pin "14") (pinfunction "DB4_14") (pintype "passive"))
    )
    (net (code "35") (name "Net-(J7-DB5)") (class "Default")
      (node (ref "J7") (pin "11") (pinfunction "DB5_11") (pintype "passive"))
      (node (ref "LCD-MODULE") (pin "13") (pinfunction "DB5_13") (pintype "passive"))
    )
    (net (code "36") (name "Net-(J7-DB6)") (class "Default")
      (node (ref "J7") (pin "12") (pinfunction "DB6_12") (pintype "passive"))
      (node (ref "LCD-MODULE") (pin "12") (pinfunction "DB6_12") (pintype "passive"))
    )
    (net (code "37") (name "Net-(J7-DB7)") (class "Default")
      (node (ref "J7") (pin "13") (pinfunction "DB7_13") (pintype "passive"))
      (node (ref "LCD-MODULE") (pin "11") (pinfunction "DB7_11") (pintype "passive"))
    )
    (net (code "38") (name "Net-(J7-DB8)") (class "Default")
      (node (ref "J7") (pin "14") (pinfunction "DB8_14") (pintype "passive"))
      (node (ref "LCD-MODULE") (pin "3") (pinfunction "DB8_3") (pintype "passive"))
    )
    (net (code "39") (name "Net-(J7-DB9)") (class "Default")
      (node (ref "J7") (pin "15") (pinfunction "DB9_15") (pintype "passive"))
      (node (ref "LCD-MODULE") (pin "4") (pinfunction "DB9_4") (pintype "passive"))
    )
    (net (code "40") (name "Net-(J7-DB10)") (class "Default")
      (node (ref "J7") (pin "16") (pinfunction "DB10_16") (pintype "passive"))
      (node (ref "LCD-MODULE") (pin "5") (pinfunction "DB10_5") (pintype "passive"))
    )
    (net (code "41") (name "Net-(J7-DB11)") (class "Default")
      (node (ref "J7") (pin "17") (pinfunction "DB11_17") (pintype "passive"))
      (node (ref "LCD-MODULE") (pin "6") (pinfunction "DB11_6") (pintype "passive"))
    )
    (net (code "42") (name "Net-(J7-DB12)") (class "Default")
      (node (ref "J7") (pin "18") (pinfunction "DB12_18") (pintype "passive"))
      (node (ref "LCD-MODULE") (pin "7") (pinfunction "DB12_7") (pintype "passive"))
    )
    (net (code "43") (name "Net-(J7-DB13)") (class "Default")
      (node (ref "J7") (pin "19") (pinfunction "DB13_19") (pintype "passive"))
      (node (ref "LCD-MODULE") (pin "8") (pinfunction "DB13_8") (pintype "passive"))
    )
    (net (code "44") (name "Net-(J7-DB14)") (class "Default")
      (node (ref "J7") (pin "20") (pinfunction "DB14_20") (pintype "passive"))
      (node (ref "LCD-MODULE") (pin "9") (pinfunction "DB14_9") (pintype "passive"))
    )
    (net (code "45") (name "Net-(J7-DB15)") (class "Default")
      (node (ref "J7") (pin "21") (pinfunction "DB15_21") (pintype "passive"))
      (node (ref "LCD-MODULE") (pin "10") (pinfunction "DB15_10") (pintype "passive"))
    )
    (net (code "46") (name "Net-(J7-RD)") (class "Default")
      (node (ref "J7") (pin "4") (pinfunction "RD_4") (pintype "passive"))
      (node (ref "LCD-MODULE") (pin "26") (pinfunction "LCD_RD_26") (pintype "passive"))
    )
    (net (code "47") (name "Net-(J7-RS)") (class "Default")
      (node (ref "J7") (pin "2") (pinfunction "RS_2") (pintype "passive"))
      (node (ref "LCD-MODULE") (pin "19") (pinfunction "LCD_RS_19") (pintype "passive"))
    )
    (net (code "48") (name "Net-(J7-RST)") (class "Default")
      (node (ref "J7") (pin "5") (pinfunction "RST_5") (pintype "passive"))
      (node (ref "LCD-MODULE") (pin "22") (pinfunction "LCD_RST_22") (pintype "passive"))
    )
    (net (code "49") (name "Net-(J7-WR)") (class "Default")
      (node (ref "J7") (pin "3") (pinfunction "WR_3") (pintype "passive"))
      (node (ref "LCD-MODULE") (pin "20") (pinfunction "LCD_WR_20") (pintype "passive"))
    )
    (net (code "50") (name "Net-(MOTHERBOARD-1)") (class "Default")
      (node (ref "F2") (pin "2") (pinfunction "2_2") (pintype "passive"))
      (node (ref "MOTHERBOARD") (pin "2") (pinfunction "1_2") (pintype "passive"))
    )
    (net (code "51") (name "Net-(R1-W)") (class "Default")
      (node (ref "R1") (pin "2") (pinfunction "W_2") (pintype "passive"))
      (node (ref "U2") (pin "7") (pinfunction "CH6_7") (pintype "passive"))
    )
    (net (code "52") (name "Net-(R2-W)") (class "Default")
      (node (ref "R2") (pin "2") (pinfunction "W_2") (pintype "passive"))
      (node (ref "U2") (pin "8") (pinfunction "CH7_8") (pintype "passive"))
    )
    (net (code "53") (name "Net-(U1-CH0)") (class "Default")
      (node (ref "R9") (pin "1") (pinfunction "1_1") (pintype "passive"))
      (node (ref "S8") (pin "1") (pinfunction "A_1") (pintype "passive"))
      (node (ref "S8") (pin "2") (pinfunction "A_2") (pintype "passive"))
      (node (ref "U1") (pin "1") (pinfunction "CH0_1") (pintype "passive"))
    )
    (net (code "54") (name "Net-(U1-CH1)") (class "Default")
      (node (ref "R10") (pin "1") (pinfunction "1_1") (pintype "passive"))
      (node (ref "S7") (pin "1") (pinfunction "A_1") (pintype "passive"))
      (node (ref "S7") (pin "2") (pinfunction "A_2") (pintype "passive"))
      (node (ref "U1") (pin "2") (pinfunction "CH1_2") (pintype "passive"))
    )
    (net (code "55") (name "Net-(U1-CH2)") (class "Default")
      (node (ref "R8") (pin "1") (pinfunction "1_1") (pintype "passive"))
      (node (ref "S6") (pin "1") (pinfunction "A_1") (pintype "passive"))
      (node (ref "S6") (pin "2") (pinfunction "A_2") (pintype "passive"))
      (node (ref "U1") (pin "3") (pinfunction "CH2_3") (pintype "passive"))
    )
    (net (code "56") (name "Net-(U1-CH3)") (class "Default")
      (node (ref "R7") (pin "1") (pinfunction "1_1") (pintype "passive"))
      (node (ref "S5") (pin "1") (pinfunction "A_1") (pintype "passive"))
      (node (ref "S5") (pin "2") (pinfunction "A_2") (pintype "passive"))
      (node (ref "U1") (pin "4") (pinfunction "CH3_4") (pintype "passive"))
    )
    (net (code "57") (name "Net-(U1-CH4)") (class "Default")
      (node (ref "R6") (pin "1") (pinfunction "1_1") (pintype "passive"))
      (node (ref "S4") (pin "1") (pinfunction "A_1") (pintype "passive"))
      (node (ref "S4") (pin "2") (pinfunction "A_2") (pintype "passive"))
      (node (ref "U1") (pin "5") (pinfunction "CH4_5") (pintype "passive"))
    )
    (net (code "58") (name "Net-(U1-CH5)") (class "Default")
      (node (ref "R5") (pin "1") (pinfunction "1_1") (pintype "passive"))
      (node (ref "S3") (pin "1") (pinfunction "A_1") (pintype "passive"))
      (node (ref "S3") (pin "2") (pinfunction "A_2") (pintype "passive"))
      (node (ref "U1") (pin "6") (pinfunction "CH5_6") (pintype "passive"))
    )
    (net (code "59") (name "Net-(U1-CH6)") (class "Default")
      (node (ref "R4") (pin "1") (pinfunction "1_1") (pintype "passive"))
      (node (ref "S2") (pin "1") (pinfunction "A_1") (pintype "passive"))
      (node (ref "S2") (pin "2") (pinfunction "A_2") (pintype "passive"))
      (node (ref "U1") (pin "7") (pinfunction "CH6_7") (pintype "passive"))
    )
    (net (code "60") (name "Net-(U1-CH7)") (class "Default")
      (node (ref "R3") (pin "1") (pinfunction "1_1") (pintype "passive"))
      (node (ref "S1") (pin "1") (pinfunction "A_1") (pintype "passive"))
      (node (ref "S1") (pin "2") (pinfunction "A_2") (pintype "passive"))
      (node (ref "U1") (pin "8") (pinfunction "CH7_8") (pintype "passive"))
    )
    (net (code "61") (name "Net-(U2-CH0)") (class "Default")
      (node (ref "R16") (pin "1") (pinfunction "1_1") (pintype "passive"))
      (node (ref "S14") (pin "1") (pinfunction "A_1") (pintype "passive"))
      (node (ref "S14") (pin "2") (pinfunction "A_2") (pintype "passive"))
      (node (ref "U2") (pin "1") (pinfunction "CH0_1") (pintype "passive"))
    )
    (net (code "62") (name "Net-(U2-CH1)") (class "Default")
      (node (ref "R15") (pin "1") (pinfunction "1_1") (pintype "passive"))
      (node (ref "S13") (pin "1") (pinfunction "A_1") (pintype "passive"))
      (node (ref "S13") (pin "2") (pinfunction "A_2") (pintype "passive"))
      (node (ref "U2") (pin "2") (pinfunction "CH1_2") (pintype "passive"))
    )
    (net (code "63") (name "Net-(U2-CH2)") (class "Default")
      (node (ref "R14") (pin "1") (pinfunction "1_1") (pintype "passive"))
      (node (ref "S12") (pin "1") (pinfunction "A_1") (pintype "passive"))
      (node (ref "S12") (pin "2") (pinfunction "A_2") (pintype "passive"))
      (node (ref "U2") (pin "3") (pinfunction "CH2_3") (pintype "passive"))
    )
    (net (code "64") (name "Net-(U2-CH3)") (class "Default")
      (node (ref "R13") (pin "1") (pinfunction "1_1") (pintype "passive"))
      (node (ref "S11") (pin "1") (pinfunction "A_1") (pintype "passive"))
      (node (ref "S11") (pin "2") (pinfunction "A_2") (pintype "passive"))
      (node (ref "U2") (pin "4") (pinfunction "CH3_4") (pintype "passive"))
    )
    (net (code "65") (name "Net-(U2-CH4)") (class "Default")
      (node (ref "R12") (pin "1") (pinfunction "1_1") (pintype "passive"))
      (node (ref "S10") (pin "1") (pinfunction "A_1") (pintype "passive"))
      (node (ref "S10") (pin "2") (pinfunction "A_2") (pintype "passive"))
      (node (ref "U2") (pin "5") (pinfunction "CH4_5") (pintype "passive"))
    )
    (net (code "66") (name "Net-(U2-CH5)") (class "Default")
      (node (ref "R11") (pin "1") (pinfunction "1_1") (pintype "passive"))
      (node (ref "S9") (pin "1") (pinfunction "A_1") (pintype "passive"))
      (node (ref "S9") (pin "2") (pinfunction "A_2") (pintype "passive"))
      (node (ref "U2") (pin "6") (pinfunction "CH5_6") (pintype "passive"))
    )
    (net (code "67") (name "Net-(U3-CH0)") (class "Default")
      (node (ref "R29") (pin "1") (pinfunction "1_1") (pintype "passive"))
      (node (ref "S23") (pin "1") (pinfunction "A_1") (pintype "passive"))
      (node (ref "S23") (pin "2") (pinfunction "A_2") (pintype "passive"))
      (node (ref "U3") (pin "1") (pinfunction "CH0_1") (pintype "passive"))
    )
    (net (code "68") (name "Net-(U3-CH1)") (class "Default")
      (node (ref "R30") (pin "1") (pinfunction "1_1") (pintype "passive"))
      (node (ref "S22") (pin "1") (pinfunction "A_1") (pintype "passive"))
      (node (ref "S22") (pin "2") (pinfunction "A_2") (pintype "passive"))
      (node (ref "U3") (pin "2") (pinfunction "CH1_2") (pintype "passive"))
    )
    (net (code "69") (name "Net-(U3-CH2)") (class "Default")
      (node (ref "R31") (pin "1") (pinfunction "1_1") (pintype "passive"))
      (node (ref "S21") (pin "1") (pinfunction "A_1") (pintype "passive"))
      (node (ref "S21") (pin "2") (pinfunction "A_2") (pintype "passive"))
      (node (ref "U3") (pin "3") (pinfunction "CH2_3") (pintype "passive"))
    )
    (net (code "70") (name "Net-(U3-CH3)") (class "Default")
      (node (ref "R32") (pin "1") (pinfunction "1_1") (pintype "passive"))
      (node (ref "S20") (pin "1") (pinfunction "A_1") (pintype "passive"))
      (node (ref "S20") (pin "2") (pinfunction "A_2") (pintype "passive"))
      (node (ref "U3") (pin "4") (pinfunction "CH3_4") (pintype "passive"))
    )
    (net (code "71") (name "Net-(U3-CH4)") (class "Default")
      (node (ref "R33") (pin "1") (pinfunction "1_1") (pintype "passive"))
      (node (ref "S19") (pin "1") (pinfunction "A_1") (pintype "passive"))
      (node (ref "S19") (pin "2") (pinfunction "A_2") (pintype "passive"))
      (node (ref "U3") (pin "5") (pinfunction "CH4_5") (pintype "passive"))
    )
    (net (code "72") (name "Net-(U3-CH5)") (class "Default")
      (node (ref "R34") (pin "1") (pinfunction "1_1") (pintype "passive"))
      (node (ref "S18") (pin "1") (pinfunction "A_1") (pintype "passive"))
      (node (ref "S18") (pin "2") (pinfunction "A_2") (pintype "passive"))
      (node (ref "U3") (pin "6") (pinfunction "CH5_6") (pintype "passive"))
    )
    (net (code "73") (name "Net-(U3-CH6)") (class "Default")
      (node (ref "R35") (pin "1") (pinfunction "1_1") (pintype "passive"))
      (node (ref "S17") (pin "1") (pinfunction "A_1") (pintype "passive"))
      (node (ref "S17") (pin "2") (pinfunction "A_2") (pintype "passive"))
      (node (ref "U3") (pin "7") (pinfunction "CH6_7") (pintype "passive"))
    )
    (net (code "74") (name "Net-(U3-CH7)") (class "Default")
      (node (ref "R36") (pin "1") (pinfunction "1_1") (pintype "passive"))
      (node (ref "S16") (pin "1") (pinfunction "A_1") (pintype "passive"))
      (node (ref "S16") (pin "2") (pinfunction "A_2") (pintype "passive"))
      (node (ref "U3") (pin "8") (pinfunction "CH7_8") (pintype "passive"))
    )
    (net (code "75") (name "VCC12_IN") (class "Default")
      (node (ref "ACCUM") (pin "2") (pinfunction "1_2") (pintype "passive"))
      (node (ref "Q1") (pin "3") (pinfunction "S_3") (pintype "passive"))
      (node (ref "R26") (pin "2") (pinfunction "2_2") (pintype "passive"))
      (node (ref "R27") (pin "2") (pinfunction "2_2") (pintype "passive"))
      (node (ref "T1") (pin "LCP") (pinfunction "P2_LCP") (pintype "passive"))
    )
    (net (code "76") (name "unconnected-(ESP-8266-GPIO0-Pad3)") (class "Default")
      (node (ref "ESP-8266") (pin "3") (pinfunction "GPIO0_3") (pintype "passive"))
    )
    (net (code "77") (name "unconnected-(ESP-8266-GPIO2-Pad2)") (class "Default")
      (node (ref "ESP-8266") (pin "2") (pinfunction "GPIO2_2") (pintype "passive"))
    )
    (net (code "78") (name "unconnected-(ESP-8266-GPIO16-Pad7)") (class "Default")
      (node (ref "ESP-8266") (pin "7") (pinfunction "GPIO16_7") (pintype "passive"))
    )
    (net (code "79") (name "unconnected-(J2-CD{slash}DAT3-Pad1)") (class "Default")
      (node (ref "J2") (pin "1") (pinfunction "CD/DAT3_1") (pintype "passive"))
    )
    (net (code "80") (name "unconnected-(J2-DAT1-Pad8)") (class "Default")
      (node (ref "J2") (pin "8") (pinfunction "DAT1_8") (pintype "passive"))
    )
    (net (code "81") (name "unconnected-(LCD-MODULE-NC-Pad23)") (class "Default")
      (node (ref "LCD-MODULE") (pin "23") (pinfunction "NC_23") (pintype "passive"))
    )
    (net (code "82") (name "unconnected-(LCD-MODULE-NC-Pad24)") (class "Default")
      (node (ref "LCD-MODULE") (pin "24") (pinfunction "NC_24") (pintype "passive"))
    )
    (net (code "83") (name "unconnected-(LCD-MODULE-NC-Pad25)") (class "Default")
      (node (ref "LCD-MODULE") (pin "25") (pinfunction "NC_25") (pintype "passive"))
    )
    (net (code "84") (name "unconnected-(LCD-MODULE-NC-Pad27)") (class "Default")
      (node (ref "LCD-MODULE") (pin "27") (pinfunction "NC_27") (pintype "passive"))
    )
    (net (code "85") (name "unconnected-(LCD-MODULE-NC-Pad28)") (class "Default")
      (node (ref "LCD-MODULE") (pin "28") (pinfunction "NC_28") (pintype "passive"))
    )
    (net (code "86") (name "unconnected-(LCD-MODULE-NC-Pad29)") (class "Default")
      (node (ref "LCD-MODULE") (pin "29") (pinfunction "NC_29") (pintype "passive"))
    )
    (net (code "87") (name "unconnected-(LCD-MODULE-NC-Pad30)") (class "Default")
      (node (ref "LCD-MODULE") (pin "30") (pinfunction "NC_30") (pintype "passive"))
    )
    (net (code "88") (name "unconnected-(LCD-MODULE-RESET-Pad37)") (class "Default")
      (node (ref "LCD-MODULE") (pin "37") (pinfunction "RESET_37") (pintype "passive"))
    )
    (net (code "89") (name "unconnected-(LCD-MODULE-SD_CLK-Pad33)") (class "Default")
      (node (ref "LCD-MODULE") (pin "33") (pinfunction "SD_CLK_33") (pintype "passive"))
    )
    (net (code "90") (name "unconnected-(LCD-MODULE-SD_CS-Pad34)") (class "Default")
      (node (ref "LCD-MODULE") (pin "34") (pinfunction "SD_CS_34") (pintype "passive"))
    )
    (net (code "91") (name "unconnected-(LCD-MODULE-SD_MISO-Pad31)") (class "Default")
      (node (ref "LCD-MODULE") (pin "31") (pinfunction "SD_MISO_31") (pintype "passive"))
    )
    (net (code "92") (name "unconnected-(LCD-MODULE-SD_MOSI-Pad32)") (class "Default")
      (node (ref "LCD-MODULE") (pin "32") (pinfunction "SD_MOSI_32") (pintype "passive"))
    )
  )
)
